# jlink072.net
KiCad netlist of a schematic drawn in Altium Designer
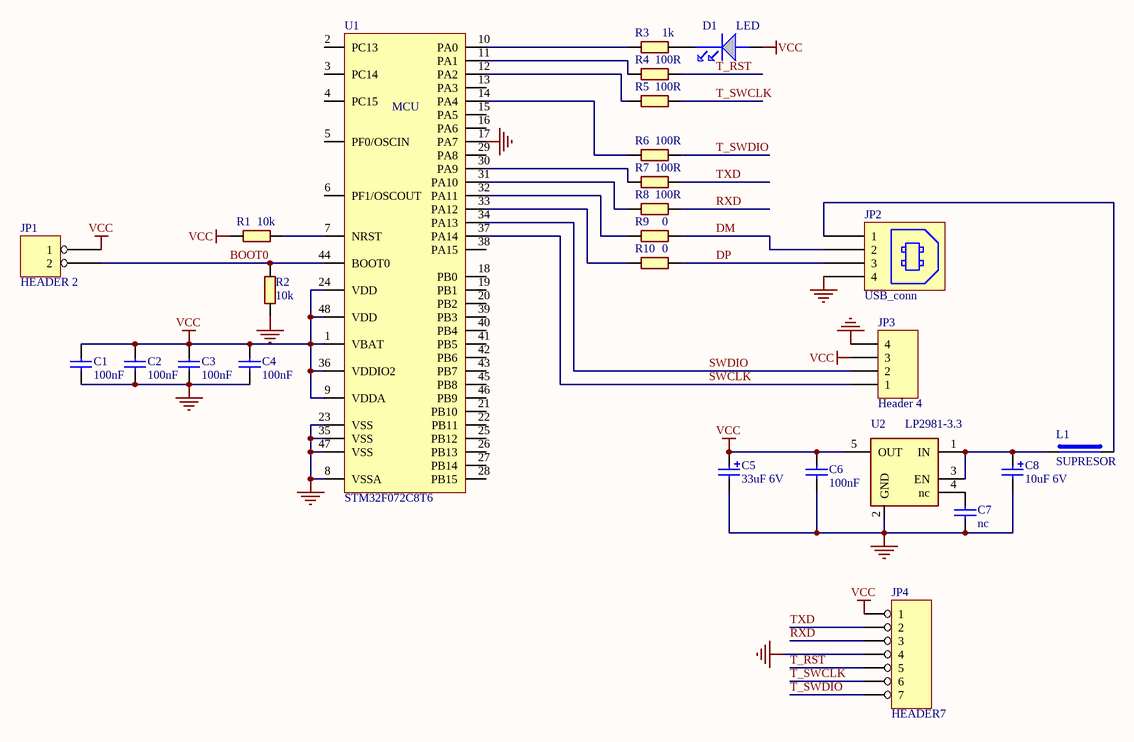
[diagram p0: jlink072.SchDoc]

(export (version "E")
  (design (tool "Eeschema 10.0.6"))
  (components
    (comp (ref "C1") (value "100nF") (footprint "C-0603") (libsource (lib "RCS-Discret") (part "CAPN")))
    (comp (ref "C2") (value "100nF") (footprint "C-0603") (libsource (lib "RCS-Discret") (part "CAPN")))
    (comp (ref "C3") (value "100nF") (footprint "C-0603") (libsource (lib "RCS-Discret") (part "CAPN")))
    (comp (ref "C4") (value "100nF") (footprint "C-0603") (libsource (lib "RCS-Discret") (part "CAPN")))
    (comp (ref "C5") (value "33uF 6V") (footprint "TANTAL-B") (libsource (lib "RCS-Discret") (part "CAPP")))
    (comp (ref "C6") (value "100nF") (footprint "C-0603") (libsource (lib "RCS-Discret") (part "CAPN")))
    (comp (ref "C7") (value "nc") (footprint "C-0603") (libsource (lib "RCS-Discret") (part "CAPN")))
    (comp (ref "C8") (value "10uF 6V") (footprint "TANTAL-A") (libsource (lib "RCS-Discret") (part "CAPP")))
    (comp (ref "D1") (value "LED") (footprint "LED-0805") (libsource (lib "RCS-Discret") (part "LED")))
    (comp (ref "JP1")
      (value "HEADER 2")
      (footprint "PLS1-2")
      (libsource (lib "Connectors") (part "HEADER 2"))
    )
    (comp (ref "JP2")
      (value "USB_conn")
      (footprint "USB_A_M_SMD")
      (description "USB_connector")
      (libsource (lib "USB_SER") (part "USB_conn"))
    )
    (comp (ref "JP3")
      (value "Header 4")
      (footprint "PLS1-4")
      (description "Header, 4-Pin")
      (fields (field (name "PUBLISHER") "Altium Limited"))
      (libsource (lib "Miscellaneous Connectors") (part "Header 4"))
    )
    (comp (ref "JP4") (value "HEADER7") (footprint "PLS1-7") (libsource (lib "Connectors") (part "HEADER7")))
    (comp (ref "L1")
      (value "SUPRESOR")
      (footprint "R-1206")
      (libsource (lib "RCS-Discret") (part "SUPRESOR"))
    )
    (comp (ref "R1") (value "10k") (footprint "R-0603") (libsource (lib "RCS-Discret") (part "RES")))
    (comp (ref "R2") (value "10k") (footprint "R-0603") (libsource (lib "") (part "RES_1")))
    (comp (ref "R3") (value "1k") (footprint "R-0603") (libsource (lib "RCS-Discret") (part "RES")))
    (comp (ref "R4") (value "100R") (footprint "R-0603") (libsource (lib "RCS-Discret") (part "RES")))
    (comp (ref "R5") (value "100R") (footprint "R-0603") (libsource (lib "RCS-Discret") (part "RES")))
    (comp (ref "R6") (value "100R") (footprint "R-0603") (libsource (lib "RCS-Discret") (part "RES")))
    (comp (ref "R7") (value "100R") (footprint "R-0603") (libsource (lib "RCS-Discret") (part "RES")))
    (comp (ref "R8") (value "100R") (footprint "R-0603") (libsource (lib "RCS-Discret") (part "RES")))
    (comp (ref "R9") (value "0") (footprint "R-0603") (libsource (lib "RCS-Discret") (part "RES")))
    (comp (ref "R10") (value "0") (footprint "R-0603") (libsource (lib "RCS-Discret") (part "RES")))
    (comp (ref "U1")
      (value "STM32F072C8T6")
      (footprint "LQFP48")
      (libsource (lib "jlink072") (part "STM32F072C8T6"))
    )
    (comp (ref "U2")
      (value "LP2981-3.3")
      (footprint "SOT-23-5")
      (libsource (lib "RCS-IMS") (part "LP2981-3.3"))
    )
  )
  (nets
    (net (code "1") (name "/BOOT0") (class "Default")
      (node (ref "JP1") (pin "2") (pinfunction "2_2") (pintype "passive"))
      (node (ref "R2") (pin "2") (pinfunction "2_2") (pintype "passive"))
      (node (ref "U1") (pin "44") (pinfunction "BOOT0_44") (pintype "passive"))
    )
    (net (code "2") (name "/DM") (class "Default")
      (node (ref "JP2") (pin "2") (pinfunction "2_2") (pintype "passive"))
      (node (ref "R9") (pin "2") (pinfunction "2_2") (pintype "passive"))
    )
    (net (code "3") (name "/DP") (class "Default")
      (node (ref "JP2") (pin "3") (pinfunction "3_3") (pintype "passive"))
      (node (ref "R10") (pin "2") (pinfunction "2_2") (pintype "passive"))
    )
    (net (code "4") (name "/RXD") (class "Default")
      (node (ref "JP4") (pin "3") (pinfunction "3_3") (pintype "passive"))
      (node (ref "R8") (pin "2") (pinfunction "2_2") (pintype "passive"))
    )
    (net (code "5") (name "/SWCLK") (class "Default")
      (node (ref "JP3") (pin "1") (pinfunction "1_1") (pintype "passive"))
      (node (ref "U1") (pin "37") (pinfunction "PA14_37") (pintype "passive"))
    )
    (net (code "6") (name "/SWDIO") (class "Default")
      (node (ref "JP3") (pin "2") (pinfunction "2_2") (pintype "passive"))
      (node (ref "U1") (pin "34") (pinfunction "PA13_34") (pintype "passive"))
    )
    (net (code "7") (name "/TXD") (class "Default")
      (node (ref "JP4") (pin "2") (pinfunction "2_2") (pintype "passive"))
      (node (ref "R7") (pin "2") (pinfunction "2_2") (pintype "passive"))
    )
    (net (code "8") (name "/T_RST") (class "Default")
      (node (ref "JP4") (pin "5") (pinfunction "5_5") (pintype "passive"))
      (node (ref "R4") (pin "2") (pinfunction "2_2") (pintype "passive"))
    )
    (net (code "9") (name "/T_SWCLK") (class "Default")
      (node (ref "JP4") (pin "6") (pinfunction "6_6") (pintype "passive"))
      (node (ref "R5") (pin "2") (pinfunction "2_2") (pintype "passive"))
    )
    (net (code "10") (name "/T_SWDIO") (class "Default")
      (node (ref "JP4") (pin "7") (pinfunction "7_7") (pintype "passive"))
      (node (ref "R6") (pin "2") (pinfunction "2_2") (pintype "passive"))
    )
    (net (code "11") (name "GND") (class "Default")
      (node (ref "C1") (pin "2") (pinfunction "2_2") (pintype "passive"))
      (node (ref "C2") (pin "2") (pinfunction "2_2") (pintype "passive"))
      (node (ref "C3") (pin "2") (pinfunction "2_2") (pintype "passive"))
      (node (ref "C4") (pin "2") (pinfunction "2_2") (pintype "passive"))
      (node (ref "C5") (pin "1") (pinfunction "1_1") (pintype "passive"))
      (node (ref "C6") (pin "2") (pinfunction "2_2") (pintype "passive"))
      (node (ref "C7") (pin "2") (pinfunction "2_2") (pintype "passive"))
      (node (ref "C8") (pin "1") (pinfunction "1_1") (pintype "passive"))
      (node (ref "JP2") (pin "4") (pinfunction "4_4") (pintype "passive"))
      (node (ref "JP3") (pin "4") (pinfunction "4_4") (pintype "passive"))
      (node (ref "JP4") (pin "4") (pinfunction "4_4") (pintype "passive"))
      (node (ref "R2") (pin "1") (pinfunction "1_1") (pintype "passive"))
      (node (ref "U1") (pin "17") (pinfunction "PA7_17") (pintype "passive"))
      (node (ref "U1") (pin "23") (pinfunction "VSS_23") (pintype "passive"))
      (node (ref "U1") (pin "35") (pinfunction "VSS_35") (pintype "passive"))
      (node (ref "U1") (pin "47") (pinfunction "VSS_47") (pintype "passive"))
      (node (ref "U1") (pin "8") (pinfunction "VSSA_8") (pintype "passive"))
      (node (ref "U2") (pin "2") (pinfunction "GND_2") (pintype "passive"))
    )
    (net (code "12") (name "Net-(D1-CATHODE)") (class "Default")
      (node (ref "D1") (pin "K") (pinfunction "CATHODE_K") (pintype "passive"))
      (node (ref "R3") (pin "2") (pinfunction "2_2") (pintype "passive"))
    )
    (net (code "13") (name "Net-(JP2-Pad1)") (class "Default")
      (node (ref "JP2") (pin "1") (pinfunction "1_1") (pintype "passive"))
      (node (ref "L1") (pin "2") (pinfunction "2_2") (pintype "passive"))
    )
    (net (code "14") (name "Net-(U1-NRST)") (class "Default")
      (node (ref "R1") (pin "2") (pinfunction "2_2") (pintype "passive"))
      (node (ref "U1") (pin "7") (pinfunction "NRST_7") (pintype "passive"))
    )
    (net (code "15") (name "Net-(U1-PA0)") (class "Default")
      (node (ref "R3") (pin "1") (pinfunction "1_1") (pintype "passive"))
      (node (ref "U1") (pin "10") (pinfunction "PA0_10") (pintype "passive"))
    )
    (net (code "16") (name "Net-(U1-PA1)") (class "Default")
      (node (ref "R4") (pin "1") (pinfunction "1_1") (pintype "passive"))
      (node (ref "U1") (pin "11") (pinfunction "PA1_11") (pintype "passive"))
    )
    (net (code "17") (name "Net-(U1-PA2)") (class "Default")
      (node (ref "R5") (pin "1") (pinfunction "1_1") (pintype "passive"))
      (node (ref "U1") (pin "12") (pinfunction "PA2_12") (pintype "passive"))
    )
    (net (code "18") (name "Net-(U1-PA4)") (class "Default")
      (node (ref "R6") (pin "1") (pinfunction "1_1") (pintype "passive"))
      (node (ref "U1") (pin "14") (pinfunction "PA4_14") (pintype "passive"))
    )
    (net (code "19") (name "Net-(U1-PA9)") (class "Default")
      (node (ref "R7") (pin "1") (pinfunction "1_1") (pintype "passive"))
      (node (ref "U1") (pin "30") (pinfunction "PA9_30") (pintype "passive"))
    )
    (net (code "20") (name "Net-(U1-PA10)") (class "Default")
      (node (ref "R8") (pin "1") (pinfunction "1_1") (pintype "passive"))
      (node (ref "U1") (pin "31") (pinfunction "PA10_31") (pintype "passive"))
    )
    (net (code "21") (name "Net-(U1-PA11)") (class "Default")
      (node (ref "R9") (pin "1") (pinfunction "1_1") (pintype "passive"))
      (node (ref "U1") (pin "32") (pinfunction "PA11_32") (pintype "passive"))
    )
    (net (code "22") (name "Net-(U1-PA12)") (class "Default")
      (node (ref "R10") (pin "1") (pinfunction "1_1") (pintype "passive"))
      (node (ref "U1") (pin "33") (pinfunction "PA12_33") (pintype "passive"))
    )
    (net (code "23") (name "Net-(U2-EN)") (class "Default")
      (node (ref "C8") (pin "2") (pinfunction "2_2") (pintype "passive"))
      (node (ref "L1") (pin "1") (pinfunction "1_1") (pintype "passive"))
      (node (ref "U2") (pin "1") (pinfunction "IN_1") (pintype "passive"))
      (node (ref "U2") (pin "3") (pinfunction "EN_3") (pintype "passive"))
    )
    (net (code "24") (name "Net-(U2-nc)") (class "Default")
      (node (ref "C7") (pin "1") (pinfunction "1_1") (pintype "passive"))
      (node (ref "U2") (pin "4") (pinfunction "nc_4") (pintype "passive"))
    )
    (net (code "25") (name "VCC") (class "Default")
      (node (ref "C1") (pin "1") (pinfunction "1_1") (pintype "passive"))
      (node (ref "C2") (pin "1") (pinfunction "1_1") (pintype "passive"))
      (node (ref "C3") (pin "1") (pinfunction "1_1") (pintype "passive"))
      (node (ref "C4") (pin "1") (pinfunction "1_1") (pintype "passive"))
      (node (ref "C5") (pin "2") (pinfunction "2_2") (pintype "passive"))
      (node (ref "C6") (pin "1") (pinfunction "1_1") (pintype "passive"))
      (node (ref "D1") (pin "A") (pinfunction "ANODE_A") (pintype "passive"))
      (node (ref "JP1") (pin "1") (pinfunction "1_1") (pintype "passive"))
      (node (ref "JP3") (pin "3") (pinfunction "3_3") (pintype "passive"))
      (node (ref "JP4") (pin "1") (pinfunction "1_1") (pintype "passive"))
      (node (ref "R1") (pin "1") (pinfunction "1_1") (pintype "passive"))
      (node (ref "U1") (pin "1") (pinfunction "VBAT_1") (pintype "passive"))
      (node (ref "U1") (pin "24") (pinfunction "VDD_24") (pintype "passive"))
      (node (ref "U1") (pin "36") (pinfunction "VDDIO2_36") (pintype "passive"))
      (node (ref "U1") (pin "48") (pinfunction "VDD_48") (pintype "passive"))
      (node (ref "U1") (pin "9") (pinfunction "VDDA_9") (pintype "passive"))
      (node (ref "U2") (pin "5") (pinfunction "OUT_5") (pintype "passive"))
    )
    (net (code "26") (name "unconnected-(U1-PA3-Pad13)") (class "Default")
      (node (ref "U1") (pin "13") (pinfunction "PA3_13") (pintype "passive"))
    )
    (net (code "27") (name "unconnected-(U1-PA5-Pad15)") (class "Default")
      (node (ref "U1") (pin "15") (pinfunction "PA5_15") (pintype "passive"))
    )
    (net (code "28") (name "unconnected-(U1-PA6-Pad16)") (class "Default")
      (node (ref "U1") (pin "16") (pinfunction "PA6_16") (pintype "passive"))
    )
    (net (code "29") (name "unconnected-(U1-PA8-Pad29)") (class "Default")
      (node (ref "U1") (pin "29") (pinfunction "PA8_29") (pintype "passive"))
    )
    (net (code "30") (name "unconnected-(U1-PA15-Pad38)") (class "Default")
      (node (ref "U1") (pin "38") (pinfunction "PA15_38") (pintype "passive"))
    )
    (net (code "31") (name "unconnected-(U1-PB0-Pad18)") (class "Default")
      (node (ref "U1") (pin "18") (pinfunction "PB0_18") (pintype "passive"))
    )
    (net (code "32") (name "unconnected-(U1-PB1-Pad19)") (class "Default")
      (node (ref "U1") (pin "19") (pinfunction "PB1_19") (pintype "passive"))
    )
    (net (code "33") (name "unconnected-(U1-PB2-Pad20)") (class "Default")
      (node (ref "U1") (pin "20") (pinfunction "PB2_20") (pintype "passive"))
    )
    (net (code "34") (name "unconnected-(U1-PB3-Pad39)") (class "Default")
      (node (ref "U1") (pin "39") (pinfunction "PB3_39") (pintype "passive"))
    )
    (net (code "35") (name "unconnected-(U1-PB4-Pad40)") (class "Default")
      (node (ref "U1") (pin "40") (pinfunction "PB4_40") (pintype "passive"))
    )
    (net (code "36") (name "unconnected-(U1-PB5-Pad41)") (class "Default")
      (node (ref "U1") (pin "41") (pinfunction "PB5_41") (pintype "passive"))
    )
    (net (code "37") (name "unconnected-(U1-PB6-Pad42)") (class "Default")
      (node (ref "U1") (pin "42") (pinfunction "PB6_42") (pintype "passive"))
    )
    (net (code "38") (name "unconnected-(U1-PB7-Pad43)") (class "Default")
      (node (ref "U1") (pin "43") (pinfunction "PB7_43") (pintype "passive"))
    )
    (net (code "39") (name "unconnected-(U1-PB8-Pad45)") (class "Default")
      (node (ref "U1") (pin "45") (pinfunction "PB8_45") (pintype "passive"))
    )
    (net (code "40") (name "unconnected-(U1-PB9-Pad46)") (class "Default")
      (node (ref "U1") (pin "46") (pinfunction "PB9_46") (pintype "passive"))
    )
    (net (code "41") (name "unconnected-(U1-PB10-Pad21)") (class "Default")
      (node (ref "U1") (pin "21") (pinfunction "PB10_21") (pintype "passive"))
    )
    (net (code "42") (name "unconnected-(U1-PB11-Pad22)") (class "Default")
      (node (ref "U1") (pin "22") (pinfunction "PB11_22") (pintype "passive"))
    )
    (net (code "43") (name "unconnected-(U1-PB12-Pad25)") (class "Default")
      (node (ref "U1") (pin "25") (pinfunction "PB12_25") (pintype "passive"))
    )
    (net (code "44") (name "unconnected-(U1-PB13-Pad26)") (class "Default")
      (node (ref "U1") (pin "26") (pinfunction "PB13_26") (pintype "passive"))
    )
    (net (code "45") (name "unconnected-(U1-PB14-Pad27)") (class "Default")
      (node (ref "U1") (pin "27") (pinfunction "PB14_27") (pintype "passive"))
    )
    (net (code "46") (name "unconnected-(U1-PB15-Pad28)") (class "Default")
      (node (ref "U1") (pin "28") (pinfunction "PB15_28") (pintype "passive"))
    )
    (net (code "47") (name "unconnected-(U1-PC13-Pad2)") (class "Default")
      (node (ref "U1") (pin "2") (pinfunction "PC13_2") (pintype "passive"))
    )
    (net (code "48") (name "unconnected-(U1-PC14-Pad3)") (class "Default")
      (node (ref "U1") (pin "3") (pinfunction "PC14_3") (pintype "passive"))
    )
    (net (code "49") (name "unconnected-(U1-PC15-Pad4)") (class "Default")
      (node (ref "U1") (pin "4") (pinfunction "PC15_4") (pintype "passive"))
    )
    (net (code "50") (name "unconnected-(U1-PF0{slash}OSCIN-Pad5)") (class "Default")
      (node (ref "U1") (pin "5") (pinfunction "PF0/OSCIN_5") (pintype "passive"))
    )
    (net (code "51") (name "unconnected-(U1-PF1{slash}OSCOUT-Pad6)") (class "Default")
      (node (ref "U1") (pin "6") (pinfunction "PF1/OSCOUT_6") (pintype "passive"))
    )
  )
)
